# VDT.net
KiCad netlist of a schematic drawn in Altium Designer
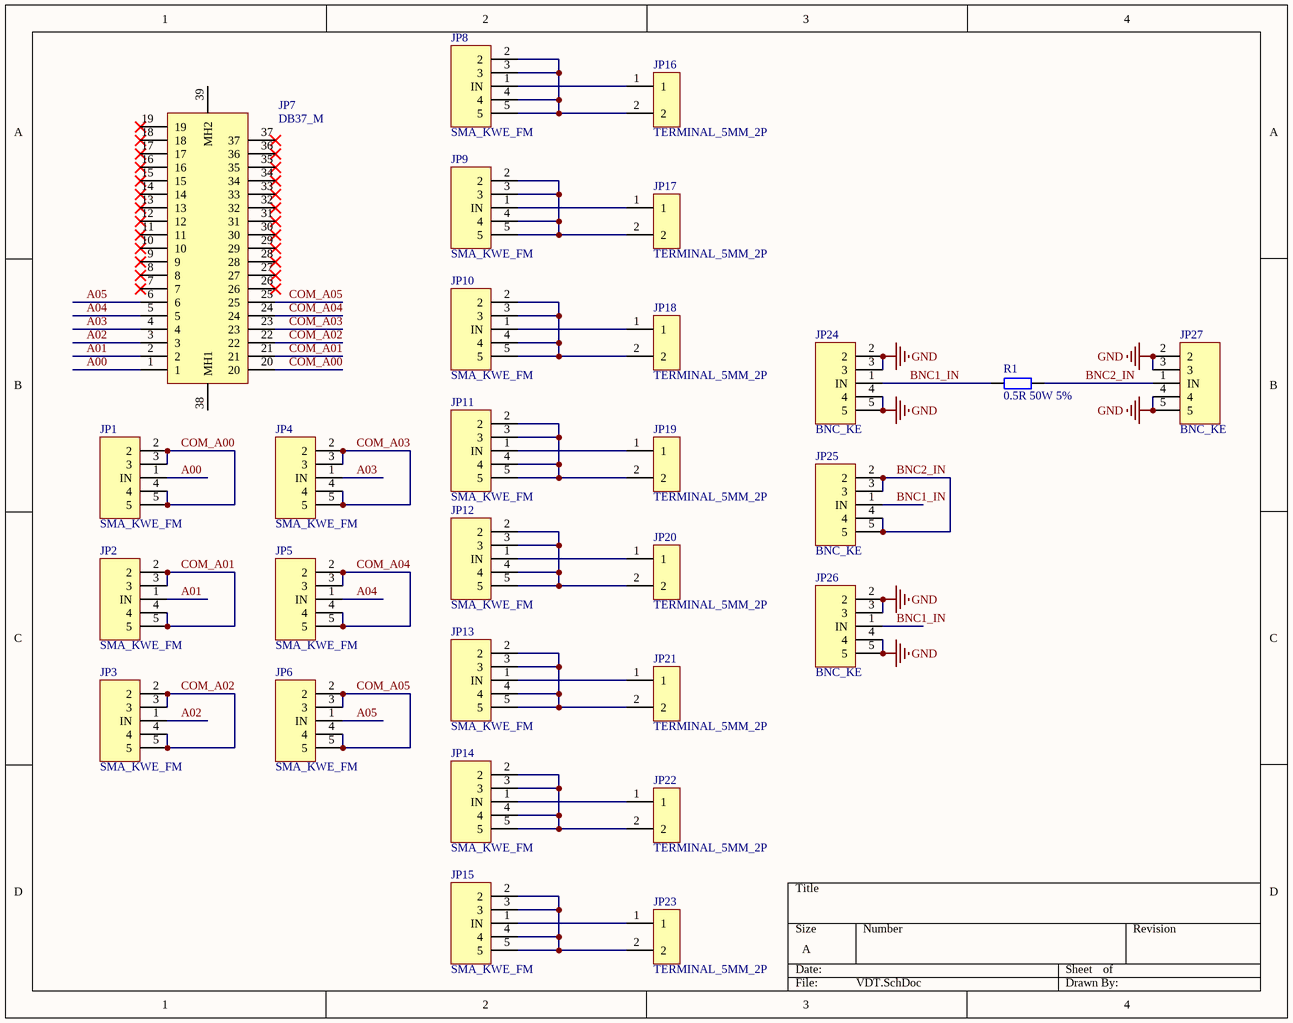
[diagram p0: VDT.SchDoc]

(export (version "E")
  (design (tool "Eeschema 10.0.6"))
  (components
    (comp (ref "JP1")
      (value "SMA_KWE_FM")
      (footprint "SMA-KWE")
      (description "SMA Connector Jack, Female Socket 50 Ohms Through Hole Solder")
      (fields
        (field (name "MANUFACTURER") "Adam Tech")
        (field (name "MANUFACTURE PART NUMBER") "RF2-04A-T-00-50-G")
      )
      (libsource (lib "Nhatkhongbuon") (part "SMA_KWE_FM"))
    )
    (comp (ref "JP2")
      (value "SMA_KWE_FM")
      (footprint "SMA-KWE")
      (description "SMA Connector Jack, Female Socket 50 Ohms Through Hole Solder")
      (fields
        (field (name "MANUFACTURER") "Adam Tech")
        (field (name "MANUFACTURE PART NUMBER") "RF2-04A-T-00-50-G")
      )
      (libsource (lib "Nhatkhongbuon") (part "SMA_KWE_FM"))
    )
    (comp (ref "JP3")
      (value "SMA_KWE_FM")
      (footprint "SMA-KWE")
      (description "SMA Connector Jack, Female Socket 50 Ohms Through Hole Solder")
      (fields
        (field (name "MANUFACTURER") "Adam Tech")
        (field (name "MANUFACTURE PART NUMBER") "RF2-04A-T-00-50-G")
      )
      (libsource (lib "Nhatkhongbuon") (part "SMA_KWE_FM"))
    )
    (comp (ref "JP4")
      (value "SMA_KWE_FM")
      (footprint "SMA-KWE")
      (description "SMA Connector Jack, Female Socket 50 Ohms Through Hole Solder")
      (fields
        (field (name "MANUFACTURER") "Adam Tech")
        (field (name "MANUFACTURE PART NUMBER") "RF2-04A-T-00-50-G")
      )
      (libsource (lib "Nhatkhongbuon") (part "SMA_KWE_FM"))
    )
    (comp (ref "JP5")
      (value "SMA_KWE_FM")
      (footprint "SMA-KWE")
      (description "SMA Connector Jack, Female Socket 50 Ohms Through Hole Solder")
      (fields
        (field (name "MANUFACTURER") "Adam Tech")
        (field (name "MANUFACTURE PART NUMBER") "RF2-04A-T-00-50-G")
      )
      (libsource (lib "Nhatkhongbuon") (part "SMA_KWE_FM"))
    )
    (comp (ref "JP6")
      (value "SMA_KWE_FM")
      (footprint "SMA-KWE")
      (description "SMA Connector Jack, Female Socket 50 Ohms Through Hole Solder")
      (fields
        (field (name "MANUFACTURER") "Adam Tech")
        (field (name "MANUFACTURE PART NUMBER") "RF2-04A-T-00-50-G")
      )
      (libsource (lib "Nhatkhongbuon") (part "SMA_KWE_FM"))
    )
    (comp (ref "JP7")
      (value "DB37_M")
      (footprint "DB37")
      (description "37 Position D-Sub Plug, Male Pins Connector")
      (fields
        (field (name "MANUFACTURER") "TE Connectivity AMP Connectors")
        (field (name "MANUFACTURE PART NUMBER") "2301836-1")
      )
      (libsource (lib "Nhatkhongbuon") (part "DB37_M"))
    )
    (comp (ref "JP8")
      (value "SMA_KWE_FM")
      (footprint "SMA-KWE")
      (description "SMA Connector Jack, Female Socket 50 Ohms Through Hole Solder")
      (fields
        (field (name "MANUFACTURER") "Adam Tech")
        (field (name "MANUFACTURE PART NUMBER") "RF2-04A-T-00-50-G")
      )
      (libsource (lib "Nhatkhongbuon") (part "SMA_KWE_FM"))
    )
    (comp (ref "JP9")
      (value "SMA_KWE_FM")
      (footprint "SMA-KWE")
      (description "SMA Connector Jack, Female Socket 50 Ohms Through Hole Solder")
      (fields
        (field (name "MANUFACTURER") "Adam Tech")
        (field (name "MANUFACTURE PART NUMBER") "RF2-04A-T-00-50-G")
      )
      (libsource (lib "Nhatkhongbuon") (part "SMA_KWE_FM"))
    )
    (comp (ref "JP10")
      (value "SMA_KWE_FM")
      (footprint "SMA-KWE")
      (description "SMA Connector Jack, Female Socket 50 Ohms Through Hole Solder")
      (fields
        (field (name "MANUFACTURER") "Adam Tech")
        (field (name "MANUFACTURE PART NUMBER") "RF2-04A-T-00-50-G")
      )
      (libsource (lib "Nhatkhongbuon") (part "SMA_KWE_FM"))
    )
    (comp (ref "JP11")
      (value "SMA_KWE_FM")
      (footprint "SMA-KWE")
      (description "SMA Connector Jack, Female Socket 50 Ohms Through Hole Solder")
      (fields
        (field (name "MANUFACTURER") "Adam Tech")
        (field (name "MANUFACTURE PART NUMBER") "RF2-04A-T-00-50-G")
      )
      (libsource (lib "Nhatkhongbuon") (part "SMA_KWE_FM"))
    )
    (comp (ref "JP12")
      (value "SMA_KWE_FM")
      (footprint "SMA-KWE")
      (description "SMA Connector Jack, Female Socket 50 Ohms Through Hole Solder")
      (fields
        (field (name "MANUFACTURER") "Adam Tech")
        (field (name "MANUFACTURE PART NUMBER") "RF2-04A-T-00-50-G")
      )
      (libsource (lib "Nhatkhongbuon") (part "SMA_KWE_FM"))
    )
    (comp (ref "JP13")
      (value "SMA_KWE_FM")
      (footprint "SMA-KWE")
      (description "SMA Connector Jack, Female Socket 50 Ohms Through Hole Solder")
      (fields
        (field (name "MANUFACTURER") "Adam Tech")
        (field (name "MANUFACTURE PART NUMBER") "RF2-04A-T-00-50-G")
      )
      (libsource (lib "Nhatkhongbuon") (part "SMA_KWE_FM"))
    )
    (comp (ref "JP14")
      (value "SMA_KWE_FM")
      (footprint "SMA-KWE")
      (description "SMA Connector Jack, Female Socket 50 Ohms Through Hole Solder")
      (fields
        (field (name "MANUFACTURER") "Adam Tech")
        (field (name "MANUFACTURE PART NUMBER") "RF2-04A-T-00-50-G")
      )
      (libsource (lib "Nhatkhongbuon") (part "SMA_KWE_FM"))
    )
    (comp (ref "JP15")
      (value "SMA_KWE_FM")
      (footprint "SMA-KWE")
      (description "SMA Connector Jack, Female Socket 50 Ohms Through Hole Solder")
      (fields
        (field (name "MANUFACTURER") "Adam Tech")
        (field (name "MANUFACTURE PART NUMBER") "RF2-04A-T-00-50-G")
      )
      (libsource (lib "Nhatkhongbuon") (part "SMA_KWE_FM"))
    )
    (comp (ref "JP16")
      (value "TERMINAL_5MM_2P")
      (footprint "TERMINAL_5MM_2P")
      (description "2 Position Wire to Board Terminal Block Horizontal with Board 0.197\" (5.00mm) Through Hole")
      (fields
        (field (name "MANUFACTURER") "Würth Elektronik")
        (field (name "MANUFACTURE PART NUMBER") "691137710002")
      )
      (libsource (lib "Nhatkhongbuon") (part "TERMINAL_5MM_2P"))
    )
    (comp (ref "JP17")
      (value "TERMINAL_5MM_2P")
      (footprint "TERMINAL_5MM_2P")
      (description "2 Position Wire to Board Terminal Block Horizontal with Board 0.197\" (5.00mm) Through Hole")
      (fields
        (field (name "MANUFACTURER") "Würth Elektronik")
        (field (name "MANUFACTURE PART NUMBER") "691137710002")
      )
      (libsource (lib "Nhatkhongbuon") (part "TERMINAL_5MM_2P"))
    )
    (comp (ref "JP18")
      (value "TERMINAL_5MM_2P")
      (footprint "TERMINAL_5MM_2P")
      (description "2 Position Wire to Board Terminal Block Horizontal with Board 0.197\" (5.00mm) Through Hole")
      (fields
        (field (name "MANUFACTURER") "Würth Elektronik")
        (field (name "MANUFACTURE PART NUMBER") "691137710002")
      )
      (libsource (lib "Nhatkhongbuon") (part "TERMINAL_5MM_2P"))
    )
    (comp (ref "JP19")
      (value "TERMINAL_5MM_2P")
      (footprint "TERMINAL_5MM_2P")
      (description "2 Position Wire to Board Terminal Block Horizontal with Board 0.197\" (5.00mm) Through Hole")
      (fields
        (field (name "MANUFACTURER") "Würth Elektronik")
        (field (name "MANUFACTURE PART NUMBER") "691137710002")
      )
      (libsource (lib "Nhatkhongbuon") (part "TERMINAL_5MM_2P"))
    )
    (comp (ref "JP20")
      (value "TERMINAL_5MM_2P")
      (footprint "TERMINAL_5MM_2P")
      (description "2 Position Wire to Board Terminal Block Horizontal with Board 0.197\" (5.00mm) Through Hole")
      (fields
        (field (name "MANUFACTURER") "Würth Elektronik")
        (field (name "MANUFACTURE PART NUMBER") "691137710002")
      )
      (libsource (lib "Nhatkhongbuon") (part "TERMINAL_5MM_2P"))
    )
    (comp (ref "JP21")
      (value "TERMINAL_5MM_2P")
      (footprint "TERMINAL_5MM_2P")
      (description "2 Position Wire to Board Terminal Block Horizontal with Board 0.197\" (5.00mm) Through Hole")
      (fields
        (field (name "MANUFACTURER") "Würth Elektronik")
        (field (name "MANUFACTURE PART NUMBER") "691137710002")
      )
      (libsource (lib "Nhatkhongbuon") (part "TERMINAL_5MM_2P"))
    )
    (comp (ref "JP22")
      (value "TERMINAL_5MM_2P")
      (footprint "TERMINAL_5MM_2P")
      (description "2 Position Wire to Board Terminal Block Horizontal with Board 0.197\" (5.00mm) Through Hole")
      (fields
        (field (name "MANUFACTURER") "Würth Elektronik")
        (field (name "MANUFACTURE PART NUMBER") "691137710002")
      )
      (libsource (lib "Nhatkhongbuon") (part "TERMINAL_5MM_2P"))
    )
    (comp (ref "JP23")
      (value "TERMINAL_5MM_2P")
      (footprint "TERMINAL_5MM_2P")
      (description "2 Position Wire to Board Terminal Block Horizontal with Board 0.197\" (5.00mm) Through Hole")
      (fields
        (field (name "MANUFACTURER") "Würth Elektronik")
        (field (name "MANUFACTURE PART NUMBER") "691137710002")
      )
      (libsource (lib "Nhatkhongbuon") (part "TERMINAL_5MM_2P"))
    )
    (comp (ref "JP24")
      (value "BNC_KE")
      (footprint "BNC-KE")
      (description "BNC Connector Jack, Female Socket 50 Ohms Through Hole Solder")
      (fields
        (field (name "MANUFACTURER") "TE Connectivity Linx")
        (field (name "MANUFACTURE PART NUMBER") "CONBNC001")
      )
      (libsource (lib "Nhatkhongbuon") (part "BNC_KE"))
    )
    (comp (ref "JP25")
      (value "BNC_KE")
      (footprint "BNC-KE")
      (description "BNC Connector Jack, Female Socket 50 Ohms Through Hole Solder")
      (fields
        (field (name "MANUFACTURER") "TE Connectivity Linx")
        (field (name "MANUFACTURE PART NUMBER") "CONBNC001")
      )
      (libsource (lib "Nhatkhongbuon") (part "BNC_KE"))
    )
    (comp (ref "JP26")
      (value "BNC_KE")
      (footprint "BNC-KE")
      (description "BNC Connector Jack, Female Socket 50 Ohms Through Hole Solder")
      (fields
        (field (name "MANUFACTURER") "TE Connectivity Linx")
        (field (name "MANUFACTURE PART NUMBER") "CONBNC001")
      )
      (libsource (lib "Nhatkhongbuon") (part "BNC_KE"))
    )
    (comp (ref "JP27")
      (value "BNC_KE")
      (footprint "BNC-KE")
      (description "BNC Connector Jack, Female Socket 50 Ohms Through Hole Solder")
      (fields
        (field (name "MANUFACTURER") "TE Connectivity Linx")
        (field (name "MANUFACTURE PART NUMBER") "CONBNC001")
      )
      (libsource (lib "") (part "BNC_KE_1"))
    )
    (comp (ref "R1")
      (value "0.5R 50W 5%")
      (footprint "HS50_P_RES")
      (description "500 mOhms ±5% 50W Wirewound Chassis Mount Resistor")
      (fields
        (field (name "MANUFACTURER") "TE Connectivity Passive Product")
        (field (name "MANUFACTURE PART NUMBER") "HSA50R50J")
      )
      (libsource (lib "Nhatkhongbuon") (part "RHS50_50W_0.5R"))
    )
  )
  (nets
    (net (code "1") (name "/A00") (class "Default")
      (node (ref "JP1") (pin "1") (pinfunction "IN_1") (pintype "passive"))
      (node (ref "JP7") (pin "1") (pinfunction "1_1") (pintype "passive"))
    )
    (net (code "2") (name "/A01") (class "Default")
      (node (ref "JP2") (pin "1") (pinfunction "IN_1") (pintype "passive"))
      (node (ref "JP7") (pin "2") (pinfunction "2_2") (pintype "passive"))
    )
    (net (code "3") (name "/A02") (class "Default")
      (node (ref "JP3") (pin "1") (pinfunction "IN_1") (pintype "passive"))
      (node (ref "JP7") (pin "3") (pinfunction "3_3") (pintype "passive"))
    )
    (net (code "4") (name "/A03") (class "Default")
      (node (ref "JP4") (pin "1") (pinfunction "IN_1") (pintype "passive"))
      (node (ref "JP7") (pin "4") (pinfunction "4_4") (pintype "passive"))
    )
    (net (code "5") (name "/A04") (class "Default")
      (node (ref "JP5") (pin "1") (pinfunction "IN_1") (pintype "passive"))
      (node (ref "JP7") (pin "5") (pinfunction "5_5") (pintype "passive"))
    )
    (net (code "6") (name "/A05") (class "Default")
      (node (ref "JP6") (pin "1") (pinfunction "IN_1") (pintype "passive"))
      (node (ref "JP7") (pin "6") (pinfunction "6_6") (pintype "passive"))
    )
    (net (code "7") (name "/BNC1_IN") (class "Default")
      (node (ref "JP24") (pin "1") (pinfunction "IN_1") (pintype "passive"))
      (node (ref "JP25") (pin "1") (pinfunction "IN_1") (pintype "passive"))
      (node (ref "JP26") (pin "1") (pinfunction "IN_1") (pintype "passive"))
      (node (ref "R1") (pin "1") (pinfunction "1_1") (pintype "passive"))
    )
    (net (code "8") (name "/BNC2_IN") (class "Default")
      (node (ref "JP25") (pin "2") (pinfunction "2_2") (pintype "passive"))
      (node (ref "JP25") (pin "3") (pinfunction "3_3") (pintype "passive"))
      (node (ref "JP25") (pin "4") (pinfunction "4_4") (pintype "passive"))
      (node (ref "JP25") (pin "5") (pinfunction "5_5") (pintype "passive"))
      (node (ref "JP27") (pin "1") (pinfunction "IN_1") (pintype "passive"))
      (node (ref "R1") (pin "2") (pinfunction "2_2") (pintype "passive"))
    )
    (net (code "9") (name "/COM_A00") (class "Default")
      (node (ref "JP1") (pin "2") (pinfunction "2_2") (pintype "passive"))
      (node (ref "JP1") (pin "3") (pinfunction "3_3") (pintype "passive"))
      (node (ref "JP1") (pin "4") (pinfunction "4_4") (pintype "passive"))
      (node (ref "JP1") (pin "5") (pinfunction "5_5") (pintype "passive"))
      (node (ref "JP7") (pin "20") (pinfunction "20_20") (pintype "passive"))
    )
    (net (code "10") (name "/COM_A01") (class "Default")
      (node (ref "JP2") (pin "2") (pinfunction "2_2") (pintype "passive"))
      (node (ref "JP2") (pin "3") (pinfunction "3_3") (pintype "passive"))
      (node (ref "JP2") (pin "4") (pinfunction "4_4") (pintype "passive"))
      (node (ref "JP2") (pin "5") (pinfunction "5_5") (pintype "passive"))
      (node (ref "JP7") (pin "21") (pinfunction "21_21") (pintype "passive"))
    )
    (net (code "11") (name "/COM_A02") (class "Default")
      (node (ref "JP3") (pin "2") (pinfunction "2_2") (pintype "passive"))
      (node (ref "JP3") (pin "3") (pinfunction "3_3") (pintype "passive"))
      (node (ref "JP3") (pin "4") (pinfunction "4_4") (pintype "passive"))
      (node (ref "JP3") (pin "5") (pinfunction "5_5") (pintype "passive"))
      (node (ref "JP7") (pin "22") (pinfunction "22_22") (pintype "passive"))
    )
    (net (code "12") (name "/COM_A03") (class "Default")
      (node (ref "JP4") (pin "2") (pinfunction "2_2") (pintype "passive"))
      (node (ref "JP4") (pin "3") (pinfunction "3_3") (pintype "passive"))
      (node (ref "JP4") (pin "4") (pinfunction "4_4") (pintype "passive"))
      (node (ref "JP4") (pin "5") (pinfunction "5_5") (pintype "passive"))
      (node (ref "JP7") (pin "23") (pinfunction "23_23") (pintype "passive"))
    )
    (net (code "13") (name "/COM_A04") (class "Default")
      (node (ref "JP5") (pin "2") (pinfunction "2_2") (pintype "passive"))
      (node (ref "JP5") (pin "3") (pinfunction "3_3") (pintype "passive"))
      (node (ref "JP5") (pin "4") (pinfunction "4_4") (pintype "passive"))
      (node (ref "JP5") (pin "5") (pinfunction "5_5") (pintype "passive"))
      (node (ref "JP7") (pin "24") (pinfunction "24_24") (pintype "passive"))
    )
    (net (code "14") (name "/COM_A05") (class "Default")
      (node (ref "JP6") (pin "2") (pinfunction "2_2") (pintype "passive"))
      (node (ref "JP6") (pin "3") (pinfunction "3_3") (pintype "passive"))
      (node (ref "JP6") (pin "4") (pinfunction "4_4") (pintype "passive"))
      (node (ref "JP6") (pin "5") (pinfunction "5_5") (pintype "passive"))
      (node (ref "JP7") (pin "25") (pinfunction "25_25") (pintype "passive"))
    )
    (net (code "15") (name "GND") (class "Default")
      (node (ref "JP24") (pin "2") (pinfunction "2_2") (pintype "passive"))
      (node (ref "JP24") (pin "3") (pinfunction "3_3") (pintype "passive"))
      (node (ref "JP24") (pin "4") (pinfunction "4_4") (pintype "passive"))
      (node (ref "JP24") (pin "5") (pinfunction "5_5") (pintype "passive"))
      (node (ref "JP26") (pin "2") (pinfunction "2_2") (pintype "passive"))
      (node (ref "JP26") (pin "3") (pinfunction "3_3") (pintype "passive"))
      (node (ref "JP26") (pin "4") (pinfunction "4_4") (pintype "passive"))
      (node (ref "JP26") (pin "5") (pinfunction "5_5") (pintype "passive"))
      (node (ref "JP27") (pin "2") (pinfunction "2_2") (pintype "passive"))
      (node (ref "JP27") (pin "3") (pinfunction "3_3") (pintype "passive"))
      (node (ref "JP27") (pin "4") (pinfunction "4_4") (pintype "passive"))
      (node (ref "JP27") (pin "5") (pinfunction "5_5") (pintype "passive"))
    )
    (net (code "16") (name "Net-(JP8-IN)") (class "Default")
      (node (ref "JP16") (pin "1") (pinfunction "1_1") (pintype "passive"))
      (node (ref "JP8") (pin "1") (pinfunction "IN_1") (pintype "passive"))
    )
    (net (code "17") (name "Net-(JP9-IN)") (class "Default")
      (node (ref "JP17") (pin "1") (pinfunction "1_1") (pintype "passive"))
      (node (ref "JP9") (pin "1") (pinfunction "IN_1") (pintype "passive"))
    )
    (net (code "18") (name "Net-(JP10-IN)") (class "Default")
      (node (ref "JP10") (pin "1") (pinfunction "IN_1") (pintype "passive"))
      (node (ref "JP18") (pin "1") (pinfunction "1_1") (pintype "passive"))
    )
    (net (code "19") (name "Net-(JP10-Pad2)") (class "Default")
      (node (ref "JP10") (pin "2") (pinfunction "2_2") (pintype "passive"))
      (node (ref "JP10") (pin "3") (pinfunction "3_3") (pintype "passive"))
      (node (ref "JP10") (pin "4") (pinfunction "4_4") (pintype "passive"))
      (node (ref "JP10") (pin "5") (pinfunction "5_5") (pintype "passive"))
      (node (ref "JP18") (pin "2") (pinfunction "2_2") (pintype "passive"))
    )
    (net (code "20") (name "Net-(JP11-IN)") (class "Default")
      (node (ref "JP11") (pin "1") (pinfunction "IN_1") (pintype "passive"))
      (node (ref "JP19") (pin "1") (pinfunction "1_1") (pintype "passive"))
    )
    (net (code "21") (name "Net-(JP11-Pad2)") (class "Default")
      (node (ref "JP11") (pin "2") (pinfunction "2_2") (pintype "passive"))
      (node (ref "JP11") (pin "3") (pinfunction "3_3") (pintype "passive"))
      (node (ref "JP11") (pin "4") (pinfunction "4_4") (pintype "passive"))
      (node (ref "JP11") (pin "5") (pinfunction "5_5") (pintype "passive"))
      (node (ref "JP19") (pin "2") (pinfunction "2_2") (pintype "passive"))
    )
    (net (code "22") (name "Net-(JP12-IN)") (class "Default")
      (node (ref "JP12") (pin "1") (pinfunction "IN_1") (pintype "passive"))
      (node (ref "JP20") (pin "1") (pinfunction "1_1") (pintype "passive"))
    )
    (net (code "23") (name "Net-(JP12-Pad2)") (class "Default")
      (node (ref "JP12") (pin "2") (pinfunction "2_2") (pintype "passive"))
      (node (ref "JP12") (pin "3") (pinfunction "3_3") (pintype "passive"))
      (node (ref "JP12") (pin "4") (pinfunction "4_4") (pintype "passive"))
      (node (ref "JP12") (pin "5") (pinfunction "5_5") (pintype "passive"))
      (node (ref "JP20") (pin "2") (pinfunction "2_2") (pintype "passive"))
    )
    (net (code "24") (name "Net-(JP13-IN)") (class "Default")
      (node (ref "JP13") (pin "1") (pinfunction "IN_1") (pintype "passive"))
      (node (ref "JP21") (pin "1") (pinfunction "1_1") (pintype "passive"))
    )
    (net (code "25") (name "Net-(JP13-Pad2)") (class "Default")
      (node (ref "JP13") (pin "2") (pinfunction "2_2") (pintype "passive"))
      (node (ref "JP13") (pin "3") (pinfunction "3_3") (pintype "passive"))
      (node (ref "JP13") (pin "4") (pinfunction "4_4") (pintype "passive"))
      (node (ref "JP13") (pin "5") (pinfunction "5_5") (pintype "passive"))
      (node (ref "JP21") (pin "2") (pinfunction "2_2") (pintype "passive"))
    )
    (net (code "26") (name "Net-(JP14-IN)") (class "Default")
      (node (ref "JP14") (pin "1") (pinfunction "IN_1") (pintype "passive"))
      (node (ref "JP22") (pin "1") (pinfunction "1_1") (pintype "passive"))
    )
    (net (code "27") (name "Net-(JP14-Pad2)") (class "Default")
      (node (ref "JP14") (pin "2") (pinfunction "2_2") (pintype "passive"))
      (node (ref "JP14") (pin "3") (pinfunction "3_3") (pintype "passive"))
      (node (ref "JP14") (pin "4") (pinfunction "4_4") (pintype "passive"))
      (node (ref "JP14") (pin "5") (pinfunction "5_5") (pintype "passive"))
      (node (ref "JP22") (pin "2") (pinfunction "2_2") (pintype "passive"))
    )
    (net (code "28") (name "Net-(JP15-IN)") (class "Default")
      (node (ref "JP15") (pin "1") (pinfunction "IN_1") (pintype "passive"))
      (node (ref "JP23") (pin "1") (pinfunction "1_1") (pintype "passive"))
    )
    (net (code "29") (name "Net-(JP15-Pad2)") (class "Default")
      (node (ref "JP15") (pin "2") (pinfunction "2_2") (pintype "passive"))
      (node (ref "JP15") (pin "3") (pinfunction "3_3") (pintype "passive"))
      (node (ref "JP15") (pin "4") (pinfunction "4_4") (pintype "passive"))
      (node (ref "JP15") (pin "5") (pinfunction "5_5") (pintype "passive"))
      (node (ref "JP23") (pin "2") (pinfunction "2_2") (pintype "passive"))
    )
    (net (code "30") (name "Net-(JP16-Pad2)") (class "Default")
      (node (ref "JP16") (pin "2") (pinfunction "2_2") (pintype "passive"))
      (node (ref "JP8") (pin "2") (pinfunction "2_2") (pintype "passive"))
      (node (ref "JP8") (pin "3") (pinfunction "3_3") (pintype "passive"))
      (node (ref "JP8") (pin "4") (pinfunction "4_4") (pintype "passive"))
      (node (ref "JP8") (pin "5") (pinfunction "5_5") (pintype "passive"))
    )
    (net (code "31") (name "Net-(JP17-Pad2)") (class "Default")
      (node (ref "JP17") (pin "2") (pinfunction "2_2") (pintype "passive"))
      (node (ref "JP9") (pin "2") (pinfunction "2_2") (pintype "passive"))
      (node (ref "JP9") (pin "3") (pinfunction "3_3") (pintype "passive"))
      (node (ref "JP9") (pin "4") (pinfunction "4_4") (pintype "passive"))
      (node (ref "JP9") (pin "5") (pinfunction "5_5") (pintype "passive"))
    )
    (net (code "32") (name "unconnected-(JP7-MH1-Pad38)") (class "Default")
      (node (ref "JP7") (pin "38") (pinfunction "MH1_38") (pintype "passive"))
    )
    (net (code "33") (name "unconnected-(JP7-MH2-Pad39)") (class "Default")
      (node (ref "JP7") (pin "39") (pinfunction "MH2_39") (pintype "passive"))
    )
    (net (code "34") (name "unconnected-(JP7-Pad7)") (class "Default")
      (node (ref "JP7") (pin "7") (pinfunction "7_7") (pintype "passive+no_connect"))
    )
    (net (code "35") (name "unconnected-(JP7-Pad8)") (class "Default")
      (node (ref "JP7") (pin "8") (pinfunction "8_8") (pintype "passive+no_connect"))
    )
    (net (code "36") (name "unconnected-(JP7-Pad9)") (class "Default")
      (node (ref "JP7") (pin "9") (pinfunction "9_9") (pintype "passive+no_connect"))
    )
    (net (code "37") (name "unconnected-(JP7-Pad10)") (class "Default")
      (node (ref "JP7") (pin "10") (pinfunction "10_10") (pintype "passive+no_connect"))
    )
    (net (code "38") (name "unconnected-(JP7-Pad11)") (class "Default")
      (node (ref "JP7") (pin "11") (pinfunction "11_11") (pintype "passive+no_connect"))
    )
    (net (code "39") (name "unconnected-(JP7-Pad12)") (class "Default")
      (node (ref "JP7") (pin "12") (pinfunction "12_12") (pintype "passive+no_connect"))
    )
    (net (code "40") (name "unconnected-(JP7-Pad13)") (class "Default")
      (node (ref "JP7") (pin "13") (pinfunction "13_13") (pintype "passive+no_connect"))
    )
    (net (code "41") (name "unconnected-(JP7-Pad14)") (class "Default")
      (node (ref "JP7") (pin "14") (pinfunction "14_14") (pintype "passive+no_connect"))
    )
    (net (code "42") (name "unconnected-(JP7-Pad15)") (class "Default")
      (node (ref "JP7") (pin "15") (pinfunction "15_15") (pintype "passive+no_connect"))
    )
    (net (code "43") (name "unconnected-(JP7-Pad16)") (class "Default")
      (node (ref "JP7") (pin "16") (pinfunction "16_16") (pintype "passive+no_connect"))
    )
    (net (code "44") (name "unconnected-(JP7-Pad17)") (class "Default")
      (node (ref "JP7") (pin "17") (pinfunction "17_17") (pintype "passive+no_connect"))
    )
    (net (code "45") (name "unconnected-(JP7-Pad18)") (class "Default")
      (node (ref "JP7") (pin "18") (pinfunction "18_18") (pintype "passive+no_connect"))
    )
    (net (code "46") (name "unconnected-(JP7-Pad19)") (class "Default")
      (node (ref "JP7") (pin "19") (pinfunction "19_19") (pintype "passive+no_connect"))
    )
    (net (code "47") (name "unconnected-(JP7-Pad26)") (class "Default")
      (node (ref "JP7") (pin "26") (pinfunction "26_26") (pintype "passive+no_connect"))
    )
    (net (code "48") (name "unconnected-(JP7-Pad27)") (class "Default")
      (node (ref "JP7") (pin "27") (pinfunction "27_27") (pintype "passive+no_connect"))
    )
    (net (code "49") (name "unconnected-(JP7-Pad28)") (class "Default")
      (node (ref "JP7") (pin "28") (pinfunction "28_28") (pintype "passive+no_connect"))
    )
    (net (code "50") (name "unconnected-(JP7-Pad29)") (class "Default")
      (node (ref "JP7") (pin "29") (pinfunction "29_29") (pintype "passive+no_connect"))
    )
    (net (code "51") (name "unconnected-(JP7-Pad30)") (class "Default")
      (node (ref "JP7") (pin "30") (pinfunction "30_30") (pintype "passive+no_connect"))
    )
    (net (code "52") (name "unconnected-(JP7-Pad31)") (class "Default")
      (node (ref "JP7") (pin "31") (pinfunction "31_31") (pintype "passive+no_connect"))
    )
    (net (code "53") (name "unconnected-(JP7-Pad32)") (class "Default")
      (node (ref "JP7") (pin "32") (pinfunction "32_32") (pintype "passive+no_connect"))
    )
    (net (code "54") (name "unconnected-(JP7-Pad33)") (class "Default")
      (node (ref "JP7") (pin "33") (pinfunction "33_33") (pintype "passive+no_connect"))
    )
    (net (code "55") (name "unconnected-(JP7-Pad34)") (class "Default")
      (node (ref "JP7") (pin "34") (pinfunction "34_34") (pintype "passive+no_connect"))
    )
    (net (code "56") (name "unconnected-(JP7-Pad35)") (class "Default")
      (node (ref "JP7") (pin "35") (pinfunction "35_35") (pintype "passive+no_connect"))
    )
    (net (code "57") (name "unconnected-(JP7-Pad36)") (class "Default")
      (node (ref "JP7") (pin "36") (pinfunction "36_36") (pintype "passive+no_connect"))
    )
    (net (code "58") (name "unconnected-(JP7-Pad37)") (class "Default")
      (node (ref "JP7") (pin "37") (pinfunction "37_37") (pintype "passive+no_connect"))
    )
  )
)
